# LSM6DSMTR.net
KiCad netlist of a schematic drawn in Altium Designer
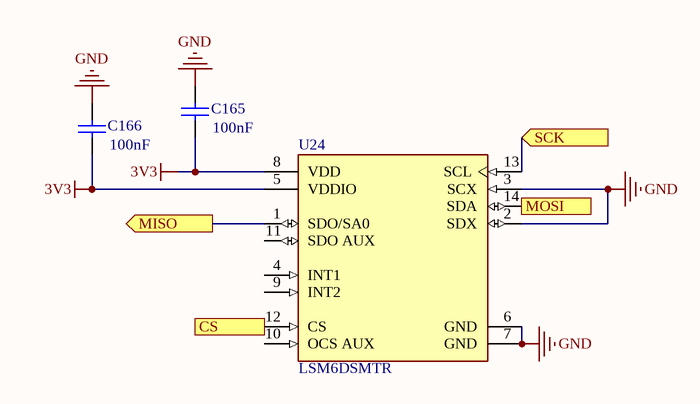
[diagram p0: LSM6DSMTR.SchDoc]

(export (version "E")
  (design (tool "Eeschema 10.0.6"))
  (components
    (comp (ref "C165")
      (value "100nF")
      (footprint "0402")
      (description "Capacitor")
      (fields (field (name "Comment") "Cap") (field (name "PUBLISHER") "Altium Limited"))
      (libsource (lib "Miscellaneous Devices") (part "Cap"))
    )
    (comp (ref "C166")
      (value "100nF")
      (footprint "0402")
      (description "Capacitor")
      (fields (field (name "Comment") "Cap") (field (name "PUBLISHER") "Altium Limited"))
      (libsource (lib "Miscellaneous Devices") (part "Cap"))
    )
    (comp (ref "U24")
      (value "LSM6DSMTR")
      (footprint "FP-LGA-14L-DM00249496-MFG")
      (description "IMU ACCEL/GYRO I2C/SPI 14LGA")
      (fields
        (field (name "OCTOPART") "https://octopart.com/lsm6dsmtr-stmicroelectronics-66358194")
        (field (name "MANUFACTURER") "STMicroelectronics")
      )
      (libsource (lib "Altium Content Vault") (part "dd82ae232bae541fa9c740d21cb9072"))
    )
  )
  (nets
    (net (code "1") (name "/CS") (class "Default")
      (node (ref "U24") (pin "12") (pinfunction "CS_12") (pintype "input"))
    )
    (net (code "2") (name "/MISO") (class "Default")
      (node (ref "U24") (pin "1") (pinfunction "SDO/SA0_1") (pintype "bidirectional"))
    )
    (net (code "3") (name "/MOSI") (class "Default")
      (node (ref "U24") (pin "14") (pinfunction "SDA_14") (pintype "bidirectional"))
    )
    (net (code "4") (name "/SCK") (class "Default")
      (node (ref "U24") (pin "13") (pinfunction "SCL_13") (pintype "input"))
    )
    (net (code "5") (name "3V3") (class "Default")
      (node (ref "C165") (pin "2") (pinfunction "2_2") (pintype "passive"))
      (node (ref "C166") (pin "2") (pinfunction "2_2") (pintype "passive"))
      (node (ref "U24") (pin "5") (pinfunction "VDDIO_5") (pintype "power_in"))
      (node (ref "U24") (pin "8") (pinfunction "VDD_8") (pintype "power_in"))
    )
    (net (code "6") (name "GND") (class "Default")
      (node (ref "C165") (pin "1") (pinfunction "1_1") (pintype "passive"))
      (node (ref "C166") (pin "1") (pinfunction "1_1") (pintype "passive"))
      (node (ref "U24") (pin "2") (pinfunction "SDX_2") (pintype "bidirectional"))
      (node (ref "U24") (pin "3") (pinfunction "SCX_3") (pintype "input"))
      (node (ref "U24") (pin "6") (pinfunction "GND_6") (pintype "power_in"))
      (node (ref "U24") (pin "7") (pinfunction "GND_7") (pintype "power_in"))
    )
    (net (code "7") (name "unconnected-(U24-INT1-Pad4)") (class "Default")
      (node (ref "U24") (pin "4") (pinfunction "INT1_4") (pintype "input"))
    )
    (net (code "8") (name "unconnected-(U24-INT2-Pad9)") (class "Default")
      (node (ref "U24") (pin "9") (pinfunction "INT2_9") (pintype "input"))
    )
    (net (code "9") (name "unconnected-(U24-OCS_AUX-Pad10)") (class "Default")
      (node (ref "U24") (pin "10") (pinfunction "OCS_AUX_10") (pintype "input"))
    )
    (net (code "10") (name "unconnected-(U24-SDO_AUX-Pad11)") (class "Default")
      (node (ref "U24") (pin "11") (pinfunction "SDO_AUX_11") (pintype "bidirectional"))
    )
  )
)
